# NusbioMCU_NeoPixels.net
KiCad netlist of a schematic drawn in EAGLE
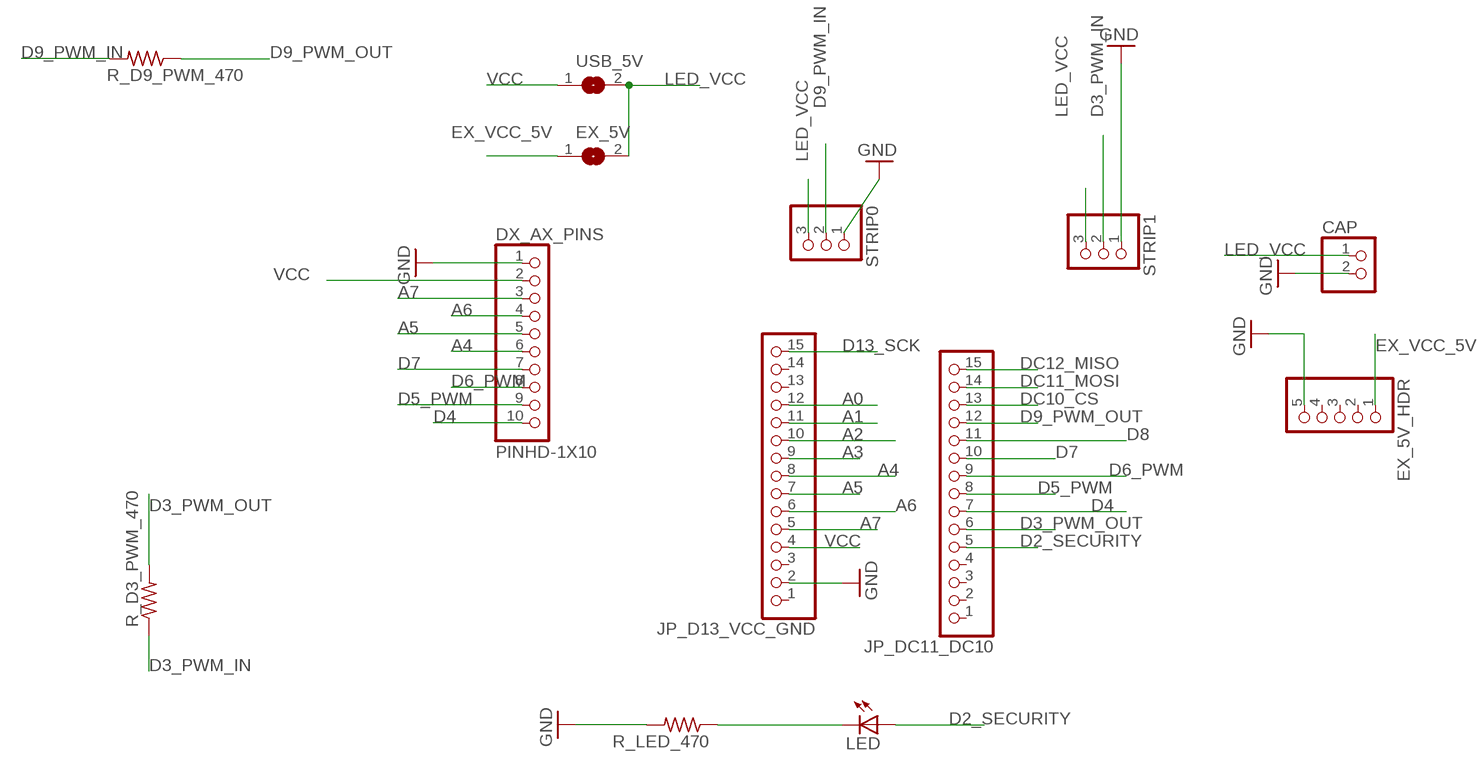
[diagram p0: schematic, sheet 1]

(export (version "E")
  (design (tool "Eeschema 10.0.6"))
  (components
    (comp (ref "CAP")
      (value "PINHD-1X2")
      (footprint "eagle-import:1X02")
      (libsource (lib "eagle-import") (part "PINHD-1X2"))
    )
    (comp (ref "DX_AX_PINS")
      (value "PINHD-1X10")
      (footprint "eagle-import:1X10-BIG")
      (libsource (lib "eagle-import") (part "PINHD-1X10"))
    )
    (comp (ref "EX_5V")
      (value "SOLDERJUMPERREFLOW")
      (footprint "eagle-import:SOLDERJUMPER_REFLOW")
      (libsource (lib "eagle-import") (part "SOLDERJUMPERREFLOW"))
    )
    (comp (ref "EX_5V_HDR")
      (value "PINHD-1X5")
      (footprint "eagle-import:1X05")
      (libsource (lib "eagle-import") (part "PINHD-1X5"))
    )
    (comp (ref "JP_D13_VCC_GND")
      (value "PINHD-1X15")
      (footprint "eagle-import:1X15")
      (libsource (lib "eagle-import") (part "PINHD-1X15"))
    )
    (comp (ref "JP_DC11_DC10")
      (value "PINHD-1X15")
      (footprint "eagle-import:1X15")
      (libsource (lib "eagle-import") (part "PINHD-1X15"))
    )
    (comp (ref "LED")
      (value "LEDSMT1206")
      (footprint "eagle-import:1206")
      (libsource (lib "eagle-import") (part "LEDSMT1206"))
    )
    (comp (ref "R_D3_PWM_470")
      (value "R-US_R1206")
      (footprint "eagle-import:R1206")
      (libsource (lib "eagle-import") (part "R-US_R1206"))
    )
    (comp (ref "R_D9_PWM_470")
      (value "R-US_R1206")
      (footprint "eagle-import:R1206")
      (libsource (lib "eagle-import") (part "R-US_R1206"))
    )
    (comp (ref "R_LED_470")
      (value "R-US_R1206")
      (footprint "eagle-import:R1206")
      (libsource (lib "eagle-import") (part "R-US_R1206"))
    )
    (comp (ref "STRIP0")
      (value "PINHD-1X3")
      (footprint "eagle-import:1X03")
      (libsource (lib "eagle-import") (part "PINHD-1X3"))
    )
    (comp (ref "STRIP1")
      (value "PINHD-1X3")
      (footprint "eagle-import:1X03")
      (libsource (lib "eagle-import") (part "PINHD-1X3"))
    )
    (comp (ref "USB_5V")
      (value "SOLDERJUMPERREFLOW")
      (footprint "eagle-import:SOLDERJUMPER_REFLOW")
      (libsource (lib "eagle-import") (part "SOLDERJUMPERREFLOW"))
    )
  )
  (nets
    (net (code "1") (name "/A0") (class "Default")
      (node (ref "JP_D13_VCC_GND") (pin "12") (pinfunction "12_12") (pintype "passive"))
    )
    (net (code "2") (name "/A1") (class "Default")
      (node (ref "JP_D13_VCC_GND") (pin "11") (pinfunction "11_11") (pintype "passive"))
    )
    (net (code "3") (name "/A2") (class "Default")
      (node (ref "JP_D13_VCC_GND") (pin "10") (pinfunction "10_10") (pintype "passive"))
    )
    (net (code "4") (name "/A3") (class "Default")
      (node (ref "JP_D13_VCC_GND") (pin "9") (pinfunction "9_9") (pintype "passive"))
    )
    (net (code "5") (name "/A4") (class "Default")
      (node (ref "DX_AX_PINS") (pin "6") (pinfunction "6_6") (pintype "passive"))
      (node (ref "JP_D13_VCC_GND") (pin "8") (pinfunction "8_8") (pintype "passive"))
    )
    (net (code "6") (name "/A5") (class "Default")
      (node (ref "DX_AX_PINS") (pin "5") (pinfunction "5_5") (pintype "passive"))
      (node (ref "JP_D13_VCC_GND") (pin "7") (pinfunction "7_7") (pintype "passive"))
    )
    (net (code "7") (name "/A6") (class "Default")
      (node (ref "DX_AX_PINS") (pin "4") (pinfunction "4_4") (pintype "passive"))
      (node (ref "JP_D13_VCC_GND") (pin "6") (pinfunction "6_6") (pintype "passive"))
    )
    (net (code "8") (name "/A7") (class "Default")
      (node (ref "DX_AX_PINS") (pin "3") (pinfunction "3_3") (pintype "passive"))
      (node (ref "JP_D13_VCC_GND") (pin "5") (pinfunction "5_5") (pintype "passive"))
    )
    (net (code "9") (name "/D2_SECURITY") (class "Default")
      (node (ref "JP_DC11_DC10") (pin "5") (pinfunction "5_5") (pintype "passive"))
      (node (ref "LED") (pin "A") (pinfunction "A_A") (pintype "passive"))
    )
    (net (code "10") (name "/D3_PWM_IN") (class "Default")
      (node (ref "R_D3_PWM_470") (pin "1") (pinfunction "1_1") (pintype "passive"))
      (node (ref "STRIP1") (pin "2") (pinfunction "2_2") (pintype "passive"))
    )
    (net (code "11") (name "/D3_PWM_OUT") (class "Default")
      (node (ref "JP_DC11_DC10") (pin "6") (pinfunction "6_6") (pintype "passive"))
      (node (ref "R_D3_PWM_470") (pin "2") (pinfunction "2_2") (pintype "passive"))
    )
    (net (code "12") (name "/D4") (class "Default")
      (node (ref "DX_AX_PINS") (pin "10") (pinfunction "10_10") (pintype "passive"))
      (node (ref "JP_DC11_DC10") (pin "7") (pinfunction "7_7") (pintype "passive"))
    )
    (net (code "13") (name "/D5_PWM") (class "Default")
      (node (ref "DX_AX_PINS") (pin "9") (pinfunction "9_9") (pintype "passive"))
      (node (ref "JP_DC11_DC10") (pin "8") (pinfunction "8_8") (pintype "passive"))
    )
    (net (code "14") (name "/D6_PWM") (class "Default")
      (node (ref "DX_AX_PINS") (pin "8") (pinfunction "8_8") (pintype "passive"))
      (node (ref "JP_DC11_DC10") (pin "9") (pinfunction "9_9") (pintype "passive"))
    )
    (net (code "15") (name "/D7") (class "Default")
      (node (ref "DX_AX_PINS") (pin "7") (pinfunction "7_7") (pintype "passive"))
      (node (ref "JP_DC11_DC10") (pin "10") (pinfunction "10_10") (pintype "passive"))
    )
    (net (code "16") (name "/D8") (class "Default")
      (node (ref "JP_DC11_DC10") (pin "11") (pinfunction "11_11") (pintype "passive"))
    )
    (net (code "17") (name "/D9_PWM_IN") (class "Default")
      (node (ref "R_D9_PWM_470") (pin "2") (pinfunction "2_2") (pintype "passive"))
      (node (ref "STRIP0") (pin "2") (pinfunction "2_2") (pintype "passive"))
    )
    (net (code "18") (name "/D9_PWM_OUT") (class "Default")
      (node (ref "JP_DC11_DC10") (pin "12") (pinfunction "12_12") (pintype "passive"))
      (node (ref "R_D9_PWM_470") (pin "1") (pinfunction "1_1") (pintype "passive"))
    )
    (net (code "19") (name "/D13_SCK") (class "Default")
      (node (ref "JP_D13_VCC_GND") (pin "15") (pinfunction "15_15") (pintype "passive"))
    )
    (net (code "20") (name "/DC10_CS") (class "Default")
      (node (ref "JP_DC11_DC10") (pin "13") (pinfunction "13_13") (pintype "passive"))
    )
    (net (code "21") (name "/DC11_MOSI") (class "Default")
      (node (ref "JP_DC11_DC10") (pin "14") (pinfunction "14_14") (pintype "passive"))
    )
    (net (code "22") (name "/DC12_MISO") (class "Default")
      (node (ref "JP_DC11_DC10") (pin "15") (pinfunction "15_15") (pintype "passive"))
    )
    (net (code "23") (name "/EX_VCC_5V") (class "Default")
      (node (ref "EX_5V") (pin "1") (pinfunction "1_1") (pintype "passive"))
      (node (ref "EX_5V_HDR") (pin "1") (pinfunction "1_1") (pintype "passive"))
    )
    (net (code "24") (name "/LED_VCC") (class "Default")
      (node (ref "CAP") (pin "1") (pinfunction "1_1") (pintype "passive"))
      (node (ref "EX_5V") (pin "2") (pinfunction "2_2") (pintype "passive"))
      (node (ref "STRIP0") (pin "3") (pinfunction "3_3") (pintype "passive"))
      (node (ref "STRIP1") (pin "3") (pinfunction "3_3") (pintype "passive"))
      (node (ref "USB_5V") (pin "2") (pinfunction "2_2") (pintype "passive"))
    )
    (net (code "25") (name "/VCC") (class "Default")
      (node (ref "DX_AX_PINS") (pin "2") (pinfunction "2_2") (pintype "passive"))
      (node (ref "JP_D13_VCC_GND") (pin "4") (pinfunction "4_4") (pintype "passive"))
      (node (ref "USB_5V") (pin "1") (pinfunction "1_1") (pintype "passive"))
    )
    (net (code "26") (name "GND") (class "Default")
      (node (ref "CAP") (pin "2") (pinfunction "2_2") (pintype "passive"))
      (node (ref "DX_AX_PINS") (pin "1") (pinfunction "1_1") (pintype "passive"))
      (node (ref "EX_5V_HDR") (pin "5") (pinfunction "5_5") (pintype "passive"))
      (node (ref "JP_D13_VCC_GND") (pin "2") (pinfunction "2_2") (pintype "passive"))
      (node (ref "R_LED_470") (pin "2") (pinfunction "2_2") (pintype "passive"))
      (node (ref "STRIP0") (pin "1") (pinfunction "1_1") (pintype "passive"))
      (node (ref "STRIP1") (pin "1") (pinfunction "1_1") (pintype "passive"))
    )
    (net (code "27") (name "Net-(LED-PadC)") (class "Default")
      (node (ref "LED") (pin "C") (pinfunction "C_C") (pintype "passive"))
      (node (ref "R_LED_470") (pin "1") (pinfunction "1_1") (pintype "passive"))
    )
    (net (code "28") (name "unconnected-(EX_5V_HDR-Pad2)") (class "Default")
      (node (ref "EX_5V_HDR") (pin "2") (pinfunction "2_2") (pintype "passive"))
    )
    (net (code "29") (name "unconnected-(EX_5V_HDR-Pad3)") (class "Default")
      (node (ref "EX_5V_HDR") (pin "3") (pinfunction "3_3") (pintype "passive"))
    )
    (net (code "30") (name "unconnected-(EX_5V_HDR-Pad4)") (class "Default")
      (node (ref "EX_5V_HDR") (pin "4") (pinfunction "4_4") (pintype "passive"))
    )
    (net (code "31") (name "unconnected-(JP_D13_VCC_GND-Pad1)") (class "Default")
      (node (ref "JP_D13_VCC_GND") (pin "1") (pinfunction "1_1") (pintype "passive"))
    )
    (net (code "32") (name "unconnected-(JP_D13_VCC_GND-Pad3)") (class "Default")
      (node (ref "JP_D13_VCC_GND") (pin "3") (pinfunction "3_3") (pintype "passive"))
    )
    (net (code "33") (name "unconnected-(JP_D13_VCC_GND-Pad13)") (class "Default")
      (node (ref "JP_D13_VCC_GND") (pin "13") (pinfunction "13_13") (pintype "passive"))
    )
    (net (code "34") (name "unconnected-(JP_D13_VCC_GND-Pad14)") (class "Default")
      (node (ref "JP_D13_VCC_GND") (pin "14") (pinfunction "14_14") (pintype "passive"))
    )
    (net (code "35") (name "unconnected-(JP_DC11_DC10-Pad1)") (class "Default")
      (node (ref "JP_DC11_DC10") (pin "1") (pinfunction "1_1") (pintype "passive"))
    )
    (net (code "36") (name "unconnected-(JP_DC11_DC10-Pad2)") (class "Default")
      (node (ref "JP_DC11_DC10") (pin "2") (pinfunction "2_2") (pintype "passive"))
    )
    (net (code "37") (name "unconnected-(JP_DC11_DC10-Pad3)") (class "Default")
      (node (ref "JP_DC11_DC10") (pin "3") (pinfunction "3_3") (pintype "passive"))
    )
    (net (code "38") (name "unconnected-(JP_DC11_DC10-Pad4)") (class "Default")
      (node (ref "JP_DC11_DC10") (pin "4") (pinfunction "4_4") (pintype "passive"))
    )
  )
)
